# PowerRegulator.net
KiCad netlist of a schematic drawn in Altium Designer
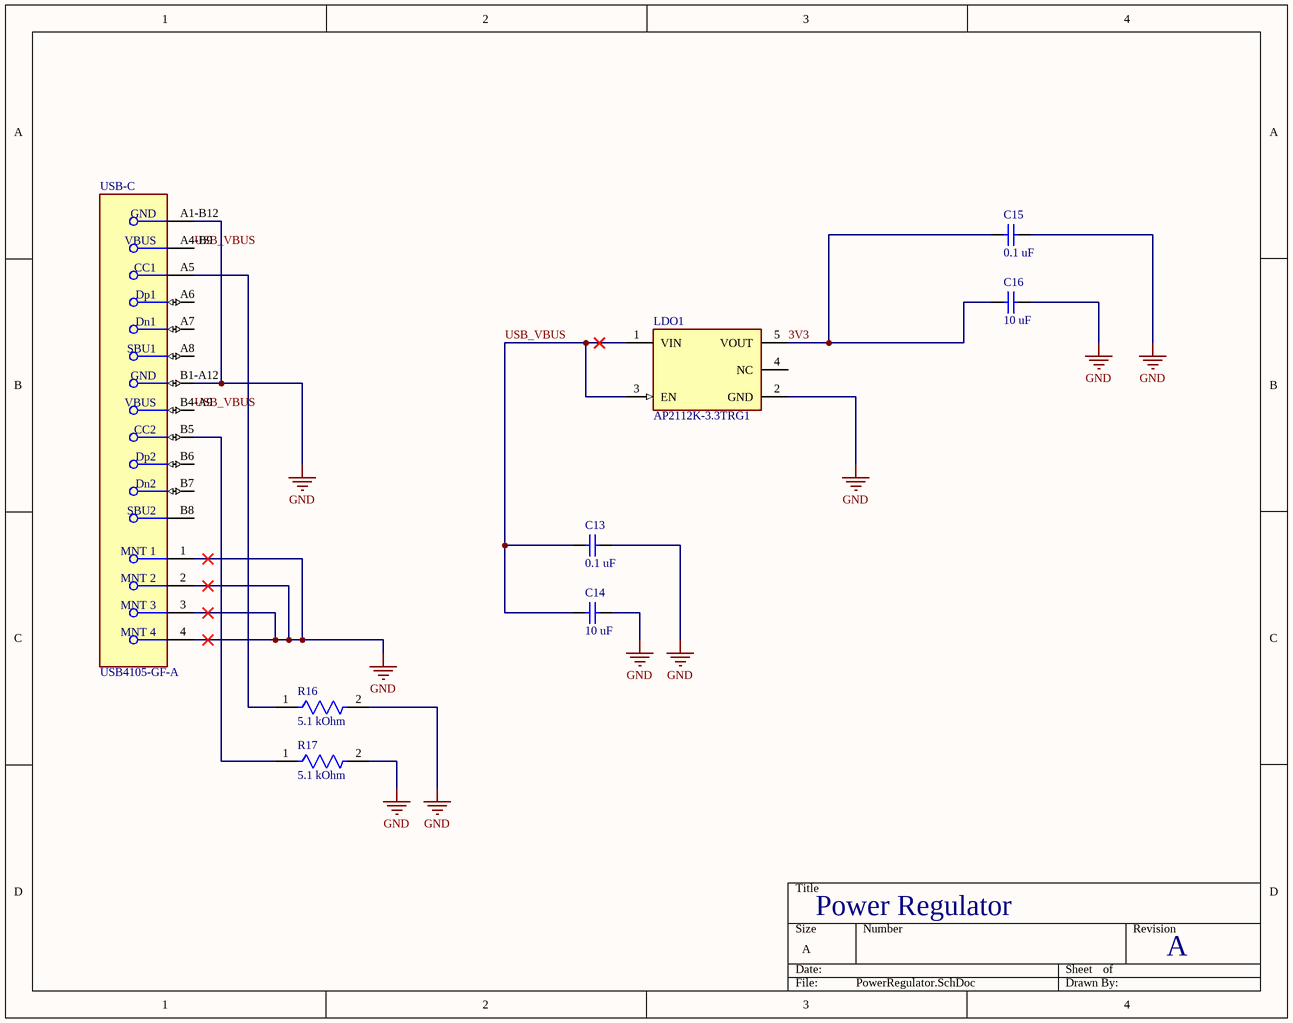
[diagram p0: PowerRegulator.SchDoc]

(export (version "E")
  (design (tool "Eeschema 10.0.6"))
  (components
    (comp (ref "C13")
      (value "0.1 uF")
      (footprint "MURA-0603_H_0.9_N")
      (description "CAP, Ceramic, 0.1 uF, 10%, 16 V, 0603, RoHS, Tape and Reel")
      (fields (field (name "MANUFACTURER") "Murata") (field (name "TOLERANCE") "10%"))
      (libsource (lib "Altium Content Vault") (part "CAP-NP-2"))
    )
    (comp (ref "C14")
      (value "10 uF")
      (footprint "MURA-0805_H_1.35_L")
      (description "CAP, Ceramic, 10 uF, 10%, 10 V, 0805, RoHS, Tape and Reel")
      (fields (field (name "MANUFACTURER") "Murata") (field (name "TOLERANCE") "±10%"))
      (libsource (lib "Altium Content Vault") (part "CAP-NP-2"))
    )
    (comp (ref "C15")
      (value "0.1 uF")
      (footprint "MURA-0603_H_0.9_N")
      (description "CAP, Ceramic, 0.1 uF, 10%, 16 V, 0603, RoHS, Tape and Reel")
      (fields (field (name "MANUFACTURER") "Murata") (field (name "TOLERANCE") "10%"))
      (libsource (lib "Altium Content Vault") (part "CAP-NP-2"))
    )
    (comp (ref "C16")
      (value "10 uF")
      (footprint "MURA-0805_H_1.35_L")
      (description "CAP, Ceramic, 10 uF, 10%, 10 V, 0805, RoHS, Tape and Reel")
      (fields (field (name "MANUFACTURER") "Murata") (field (name "TOLERANCE") "±10%"))
      (libsource (lib "Altium Content Vault") (part "CAP-NP-2"))
    )
    (comp (ref "LDO1")
      (value "AP2112K-3.3TRG1")
      (footprint "FP-SOT25-IPC_C")
      (description "IC REG LINEAR 3.3V 600MA SOT25")
      (libsource (lib "Altium Content Vault") (part "c8ab751aee5229183125ab046a11caa"))
    )
    (comp (ref "R16")
      (value "5.1 kOhm")
      (footprint "FP-RN73R1E-IPC_C")
      (description "5.1kΩ ±1% 0.063W, 1/16W Chip Resistor 0402 (1005 Metric) Moisture Resistant Thin Film")
      (libsource (lib "Altium Content Vault") (part "1029c3af85768c4190bb7ad29bc67b5"))
    )
    (comp (ref "R17")
      (value "5.1 kOhm")
      (footprint "FP-RN73R1E-IPC_C")
      (description "5.1kΩ ±1% 0.063W, 1/16W Chip Resistor 0402 (1005 Metric) Moisture Resistant Thin Film")
      (libsource (lib "Altium Content Vault") (part "1029c3af85768c4190bb7ad29bc67b5"))
    )
    (comp (ref "USB-C")
      (value "USB4105-GF-A")
      (footprint "FP-USB4105-GF-A-MFG")
      (description "CONN RCPT USB2.0 TYPEC 5A")
      (fields
        (field (name "MANUFACTURER") "GCT")
        (field (name "OCTOPART") "https://octopart.com/usb4105-gf-a-gct-106627878")
      )
      (libsource (lib "Altium Content Vault") (part "e7c17a616881a82b79941196b4bec10"))
    )
  )
  (nets
    (net (code "1") (name "/3V3") (class "Default")
      (node (ref "C15") (pin "1") (pinfunction "1_1") (pintype "passive"))
      (node (ref "C16") (pin "1") (pinfunction "1_1") (pintype "passive"))
      (node (ref "LDO1") (pin "5") (pinfunction "VOUT_5") (pintype "power_in"))
    )
    (net (code "2") (name "/USB_VBUS") (class "Default")
      (node (ref "C13") (pin "1") (pinfunction "1_1") (pintype "passive"))
      (node (ref "C14") (pin "1") (pinfunction "1_1") (pintype "passive"))
      (node (ref "LDO1") (pin "1") (pinfunction "VIN_1") (pintype "power_in"))
      (node (ref "LDO1") (pin "3") (pinfunction "EN_3") (pintype "input"))
      (node (ref "USB-C") (pin "A4-B9") (pinfunction "VBUS_A4-B9") (pintype "power_in"))
      (node (ref "USB-C") (pin "B4-A9") (pinfunction "VBUS_B4-A9") (pintype "bidirectional"))
    )
    (net (code "3") (name "GND") (class "Default")
      (node (ref "C13") (pin "2") (pinfunction "2_2") (pintype "passive"))
      (node (ref "C14") (pin "2") (pinfunction "2_2") (pintype "passive"))
      (node (ref "C15") (pin "2") (pinfunction "2_2") (pintype "passive"))
      (node (ref "C16") (pin "2") (pinfunction "2_2") (pintype "passive"))
      (node (ref "LDO1") (pin "2") (pinfunction "GND_2") (pintype "power_in"))
      (node (ref "R16") (pin "2") (pinfunction "2_2") (pintype "passive"))
      (node (ref "R17") (pin "2") (pinfunction "2_2") (pintype "passive"))
      (node (ref "USB-C") (pin "1") (pinfunction "MNT_1_1") (pintype "power_in"))
      (node (ref "USB-C") (pin "2") (pinfunction "MNT_2_2") (pintype "power_in"))
      (node (ref "USB-C") (pin "3") (pinfunction "MNT_3_3") (pintype "power_in"))
      (node (ref "USB-C") (pin "4") (pinfunction "MNT_4_4") (pintype "power_in"))
      (node (ref "USB-C") (pin "A1-B12") (pinfunction "GND_A1-B12") (pintype "power_in"))
      (node (ref "USB-C") (pin "B1-A12") (pinfunction "GND_B1-A12") (pintype "bidirectional"))
    )
    (net (code "4") (name "Net-(USB-C-CC1)") (class "Default")
      (node (ref "R16") (pin "1") (pinfunction "1_1") (pintype "passive"))
      (node (ref "USB-C") (pin "A5") (pinfunction "CC1_A5") (pintype "power_in"))
    )
    (net (code "5") (name "Net-(USB-C-CC2)") (class "Default")
      (node (ref "R17") (pin "1") (pinfunction "1_1") (pintype "passive"))
      (node (ref "USB-C") (pin "B5") (pinfunction "CC2_B5") (pintype "bidirectional"))
    )
    (net (code "6") (name "unconnected-(LDO1-NC-Pad4)") (class "Default")
      (node (ref "LDO1") (pin "4") (pinfunction "NC_4") (pintype "passive"))
    )
    (net (code "7") (name "unconnected-(USB-C-Dn1-PadA7)") (class "Default")
      (node (ref "USB-C") (pin "A7") (pinfunction "Dn1_A7") (pintype "bidirectional"))
    )
    (net (code "8") (name "unconnected-(USB-C-Dn2-PadB7)") (class "Default")
      (node (ref "USB-C") (pin "B7") (pinfunction "Dn2_B7") (pintype "bidirectional"))
    )
    (net (code "9") (name "unconnected-(USB-C-Dp1-PadA6)") (class "Default")
      (node (ref "USB-C") (pin "A6") (pinfunction "Dp1_A6") (pintype "bidirectional"))
    )
    (net (code "10") (name "unconnected-(USB-C-Dp2-PadB6)") (class "Default")
      (node (ref "USB-C") (pin "B6") (pinfunction "Dp2_B6") (pintype "bidirectional"))
    )
    (net (code "11") (name "unconnected-(USB-C-SBU1-PadA8)") (class "Default")
      (node (ref "USB-C") (pin "A8") (pinfunction "SBU1_A8") (pintype "bidirectional"))
    )
    (net (code "12") (name "unconnected-(USB-C-SBU2-PadB8)") (class "Default")
      (node (ref "USB-C") (pin "B8") (pinfunction "SBU2_B8") (pintype "power_in"))
    )
  )
)
